# core.net
KiCad netlist of a schematic drawn in Altium Designer
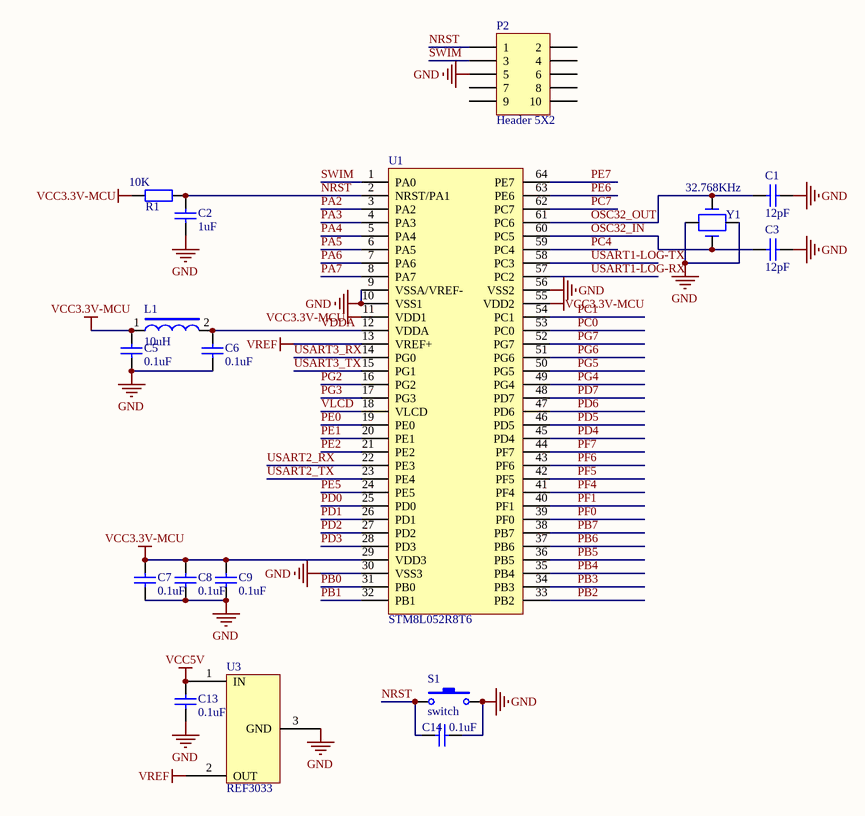
[diagram p0: core.SchDoc]

(export (version "E")
  (design (tool "Eeschema 10.0.6"))
  (components
    (comp (ref "C1")
      (value "12pF")
      (footprint "0603_C")
      (description "贴片电容，0603")
      (libsource (lib "stm8l052r8t6开发板") (part "Cap"))
    )
    (comp (ref "C2")
      (value "1uF")
      (footprint "0603_C")
      (description "贴片电容，0603")
      (libsource (lib "stm8l052r8t6开发板") (part "Cap"))
    )
    (comp (ref "C3")
      (value "12pF")
      (footprint "0603_C")
      (description "贴片电容，0603")
      (libsource (lib "stm8l052r8t6开发板") (part "Cap"))
    )
    (comp (ref "C5")
      (value "0.1uF")
      (footprint "0603_C")
      (description "贴片电容，0603")
      (libsource (lib "stm8l052r8t6开发板") (part "Cap"))
    )
    (comp (ref "C6")
      (value "0.1uF")
      (footprint "0603_C")
      (description "贴片电容，0603")
      (libsource (lib "stm8l052r8t6开发板") (part "Cap"))
    )
    (comp (ref "C7")
      (value "0.1uF")
      (footprint "0603_C")
      (description "贴片电容，0603")
      (libsource (lib "stm8l052r8t6开发板") (part "Cap"))
    )
    (comp (ref "C8")
      (value "0.1uF")
      (footprint "0603_C")
      (description "贴片电容，0603")
      (libsource (lib "stm8l052r8t6开发板") (part "Cap"))
    )
    (comp (ref "C9")
      (value "0.1uF")
      (footprint "0603_C")
      (description "贴片电容，0603")
      (libsource (lib "stm8l052r8t6开发板") (part "Cap"))
    )
    (comp (ref "C13")
      (value "0.1uF")
      (footprint "0603_C")
      (description "贴片电容，0603")
      (libsource (lib "stm8l052r8t6开发板") (part "Cap"))
    )
    (comp (ref "C14")
      (value "0.1uF")
      (footprint "0603_C")
      (description "贴片电容，0603")
      (libsource (lib "stm8l052r8t6开发板") (part "Cap"))
    )
    (comp (ref "L1")
      (value "10uH")
      (footprint "0603_L")
      (description "MLZ1608E100MT000，贴片电感，0603")
      (libsource (lib "stm8l052r8t6开发板") (part "L"))
    )
    (comp (ref "P2")
      (value "Header 5X2")
      (footprint "2.54-2*5P简牛")
      (description "2.54mm 2*5P 直 简牛")
      (libsource (lib "Miscellaneous Connectors") (part "Header 5X2"))
    )
    (comp (ref "R1")
      (value "10K")
      (footprint "0603_R")
      (description "贴片电阻，0603")
      (libsource (lib "stm8l052r8t6开发板") (part "Res2"))
    )
    (comp (ref "S1")
      (value "switch")
      (footprint "SW-SMD_4P-L6.2-W6.2-P4.50-LS9.0")
      (description "贴片按键，6*6*5")
      (libsource (lib "stm8l052r8t6开发板") (part "switch"))
    )
    (comp (ref "U1")
      (value "STM8L052R8T6")
      (footprint "LQFP-64_10X10X05P")
      (description "STM8L052R8T6,LQFP-64_10x10x05P")
      (libsource (lib "stm8l052r8t6开发板") (part "STM8L052R8T6"))
    )
    (comp (ref "U3")
      (value "REF3033")
      (footprint "SOT-23(SOT-23-3)")
      (description "3.0V标准电压输出，SOT-23")
      (fields (field (name "AUTOR") "caibin"))
      (libsource (lib "stm8l052r8t6开发板") (part "REF3033AIDBZR"))
    )
    (comp (ref "Y1")
      (value "32.768KHz")
      (footprint "CRY_MC146")
      (description "OSC,32.768KHz,+/-25ppm,3.3V,15pF,MC146,-20℃~70℃")
      (libsource (lib "stm8l052r8t6开发板") (part "CRYSTAL_1"))
    )
  )
  (nets
    (net (code "1") (name "/NRST") (class "Default")
      (node (ref "C14") (pin "1") (pinfunction "1_1") (pintype "passive"))
      (node (ref "C2") (pin "2") (pinfunction "2_2") (pintype "passive"))
      (node (ref "P2") (pin "1") (pinfunction "1_1") (pintype "passive"))
      (node (ref "R1") (pin "2") (pinfunction "2_2") (pintype "passive"))
      (node (ref "S1") (pin "1") (pinfunction "1_1") (pintype "passive"))
      (node (ref "U1") (pin "2") (pinfunction "NRST/PA1_2") (pintype "passive"))
    )
    (net (code "2") (name "/OSC32_IN") (class "Default")
      (node (ref "C3") (pin "2") (pinfunction "2_2") (pintype "passive"))
      (node (ref "U1") (pin "60") (pinfunction "PC5_60") (pintype "passive"))
      (node (ref "Y1") (pin "1") (pinfunction "1_1") (pintype "passive"))
    )
    (net (code "3") (name "/OSC32_OUT") (class "Default")
      (node (ref "C1") (pin "2") (pinfunction "2_2") (pintype "passive"))
      (node (ref "U1") (pin "61") (pinfunction "PC6_61") (pintype "passive"))
      (node (ref "Y1") (pin "2") (pinfunction "2_2") (pintype "passive"))
    )
    (net (code "4") (name "/PA2") (class "Default")
      (node (ref "U1") (pin "3") (pinfunction "PA2_3") (pintype "passive"))
    )
    (net (code "5") (name "/PA3") (class "Default")
      (node (ref "U1") (pin "4") (pinfunction "PA3_4") (pintype "passive"))
    )
    (net (code "6") (name "/PA4") (class "Default")
      (node (ref "U1") (pin "5") (pinfunction "PA4_5") (pintype "passive"))
    )
    (net (code "7") (name "/PA5") (class "Default")
      (node (ref "U1") (pin "6") (pinfunction "PA5_6") (pintype "passive"))
    )
    (net (code "8") (name "/PA6") (class "Default")
      (node (ref "U1") (pin "7") (pinfunction "PA6_7") (pintype "passive"))
    )
    (net (code "9") (name "/PA7") (class "Default")
      (node (ref "U1") (pin "8") (pinfunction "PA7_8") (pintype "passive"))
    )
    (net (code "10") (name "/PB0") (class "Default")
      (node (ref "U1") (pin "31") (pinfunction "PB0_31") (pintype "passive"))
    )
    (net (code "11") (name "/PB1") (class "Default")
      (node (ref "U1") (pin "32") (pinfunction "PB1_32") (pintype "passive"))
    )
    (net (code "12") (name "/PB2") (class "Default")
      (node (ref "U1") (pin "33") (pinfunction "PB2_33") (pintype "passive"))
    )
    (net (code "13") (name "/PB3") (class "Default")
      (node (ref "U1") (pin "34") (pinfunction "PB3_34") (pintype "passive"))
    )
    (net (code "14") (name "/PB4") (class "Default")
      (node (ref "U1") (pin "35") (pinfunction "PB4_35") (pintype "passive"))
    )
    (net (code "15") (name "/PB5") (class "Default")
      (node (ref "U1") (pin "36") (pinfunction "PB5_36") (pintype "passive"))
    )
    (net (code "16") (name "/PB6") (class "Default")
      (node (ref "U1") (pin "37") (pinfunction "PB6_37") (pintype "passive"))
    )
    (net (code "17") (name "/PB7") (class "Default")
      (node (ref "U1") (pin "38") (pinfunction "PB7_38") (pintype "passive"))
    )
    (net (code "18") (name "/PC0") (class "Default")
      (node (ref "U1") (pin "53") (pinfunction "PC0_53") (pintype "passive"))
    )
    (net (code "19") (name "/PC1") (class "Default")
      (node (ref "U1") (pin "54") (pinfunction "PC1_54") (pintype "passive"))
    )
    (net (code "20") (name "/PC4") (class "Default")
      (node (ref "U1") (pin "59") (pinfunction "PC4_59") (pintype "passive"))
    )
    (net (code "21") (name "/PC7") (class "Default")
      (node (ref "U1") (pin "62") (pinfunction "PC7_62") (pintype "passive"))
    )
    (net (code "22") (name "/PD0") (class "Default")
      (node (ref "U1") (pin "25") (pinfunction "PD0_25") (pintype "passive"))
    )
    (net (code "23") (name "/PD1") (class "Default")
      (node (ref "U1") (pin "26") (pinfunction "PD1_26") (pintype "passive"))
    )
    (net (code "24") (name "/PD2") (class "Default")
      (node (ref "U1") (pin "27") (pinfunction "PD2_27") (pintype "passive"))
    )
    (net (code "25") (name "/PD3") (class "Default")
      (node (ref "U1") (pin "28") (pinfunction "PD3_28") (pintype "passive"))
    )
    (net (code "26") (name "/PD4") (class "Default")
      (node (ref "U1") (pin "45") (pinfunction "PD4_45") (pintype "passive"))
    )
    (net (code "27") (name "/PD5") (class "Default")
      (node (ref "U1") (pin "46") (pinfunction "PD5_46") (pintype "passive"))
    )
    (net (code "28") (name "/PD6") (class "Default")
      (node (ref "U1") (pin "47") (pinfunction "PD6_47") (pintype "passive"))
    )
    (net (code "29") (name "/PD7") (class "Default")
      (node (ref "U1") (pin "48") (pinfunction "PD7_48") (pintype "passive"))
    )
    (net (code "30") (name "/PE0") (class "Default")
      (node (ref "U1") (pin "19") (pinfunction "PE0_19") (pintype "passive"))
    )
    (net (code "31") (name "/PE1") (class "Default")
      (node (ref "U1") (pin "20") (pinfunction "PE1_20") (pintype "passive"))
    )
    (net (code "32") (name "/PE2") (class "Default")
      (node (ref "U1") (pin "21") (pinfunction "PE2_21") (pintype "passive"))
    )
    (net (code "33") (name "/PE5") (class "Default")
      (node (ref "U1") (pin "24") (pinfunction "PE5_24") (pintype "passive"))
    )
    (net (code "34") (name "/PE6") (class "Default")
      (node (ref "U1") (pin "63") (pinfunction "PE6_63") (pintype "passive"))
    )
    (net (code "35") (name "/PE7") (class "Default")
      (node (ref "U1") (pin "64") (pinfunction "PE7_64") (pintype "passive"))
    )
    (net (code "36") (name "/PF0") (class "Default")
      (node (ref "U1") (pin "39") (pinfunction "PF0_39") (pintype "passive"))
    )
    (net (code "37") (name "/PF1") (class "Default")
      (node (ref "U1") (pin "40") (pinfunction "PF1_40") (pintype "passive"))
    )
    (net (code "38") (name "/PF4") (class "Default")
      (node (ref "U1") (pin "41") (pinfunction "PF4_41") (pintype "passive"))
    )
    (net (code "39") (name "/PF5") (class "Default")
      (node (ref "U1") (pin "42") (pinfunction "PF5_42") (pintype "passive"))
    )
    (net (code "40") (name "/PF6") (class "Default")
      (node (ref "U1") (pin "43") (pinfunction "PF6_43") (pintype "passive"))
    )
    (net (code "41") (name "/PF7") (class "Default")
      (node (ref "U1") (pin "44") (pinfunction "PF7_44") (pintype "passive"))
    )
    (net (code "42") (name "/PG2") (class "Default")
      (node (ref "U1") (pin "16") (pinfunction "PG2_16") (pintype "passive"))
    )
    (net (code "43") (name "/PG3") (class "Default")
      (node (ref "U1") (pin "17") (pinfunction "PG3_17") (pintype "passive"))
    )
    (net (code "44") (name "/PG4") (class "Default")
      (node (ref "U1") (pin "49") (pinfunction "PG4_49") (pintype "passive"))
    )
    (net (code "45") (name "/PG5") (class "Default")
      (node (ref "U1") (pin "50") (pinfunction "PG5_50") (pintype "passive"))
    )
    (net (code "46") (name "/PG6") (class "Default")
      (node (ref "U1") (pin "51") (pinfunction "PG6_51") (pintype "passive"))
    )
    (net (code "47") (name "/PG7") (class "Default")
      (node (ref "U1") (pin "52") (pinfunction "PG7_52") (pintype "passive"))
    )
    (net (code "48") (name "/SWIM") (class "Default")
      (node (ref "P2") (pin "3") (pinfunction "3_3") (pintype "passive"))
      (node (ref "U1") (pin "1") (pinfunction "PA0_1") (pintype "passive"))
    )
    (net (code "49") (name "/USART1-LOG-RX") (class "Default")
      (node (ref "U1") (pin "57") (pinfunction "PC2_57") (pintype "passive"))
    )
    (net (code "50") (name "/USART1-LOG-TX") (class "Default")
      (node (ref "U1") (pin "58") (pinfunction "PC3_58") (pintype "passive"))
    )
    (net (code "51") (name "/USART2_RX") (class "Default")
      (node (ref "U1") (pin "22") (pinfunction "PE3_22") (pintype "passive"))
    )
    (net (code "52") (name "/USART2_TX") (class "Default")
      (node (ref "U1") (pin "23") (pinfunction "PE4_23") (pintype "passive"))
    )
    (net (code "53") (name "/USART3_RX") (class "Default")
      (node (ref "U1") (pin "14") (pinfunction "PG0_14") (pintype "passive"))
    )
    (net (code "54") (name "/USART3_TX") (class "Default")
      (node (ref "U1") (pin "15") (pinfunction "PG1_15") (pintype "passive"))
    )
    (net (code "55") (name "/VDDA") (class "Default")
      (node (ref "C6") (pin "2") (pinfunction "2_2") (pintype "passive"))
      (node (ref "L1") (pin "2") (pintype "passive"))
      (node (ref "U1") (pin "12") (pinfunction "VDDA_12") (pintype "passive"))
    )
    (net (code "56") (name "/VLCD") (class "Default")
      (node (ref "U1") (pin "18") (pinfunction "VLCD_18") (pintype "passive"))
    )
    (net (code "57") (name "GND") (class "Default")
      (node (ref "C1") (pin "1") (pinfunction "1_1") (pintype "passive"))
      (node (ref "C13") (pin "1") (pinfunction "1_1") (pintype "passive"))
      (node (ref "C14") (pin "2") (pinfunction "2_2") (pintype "passive"))
      (node (ref "C2") (pin "1") (pinfunction "1_1") (pintype "passive"))
      (node (ref "C3") (pin "1") (pinfunction "1_1") (pintype "passive"))
      (node (ref "C5") (pin "1") (pinfunction "1_1") (pintype "passive"))
      (node (ref "C6") (pin "1") (pinfunction "1_1") (pintype "passive"))
      (node (ref "C7") (pin "1") (pinfunction "1_1") (pintype "passive"))
      (node (ref "C8") (pin "1") (pinfunction "1_1") (pintype "passive"))
      (node (ref "C9") (pin "1") (pinfunction "1_1") (pintype "passive"))
      (node (ref "P2") (pin "5") (pinfunction "5_5") (pintype "passive"))
      (node (ref "S1") (pin "2") (pinfunction "2_2") (pintype "passive"))
      (node (ref "U1") (pin "10") (pinfunction "VSS1_10") (pintype "passive"))
      (node (ref "U1") (pin "30") (pinfunction "VSS3_30") (pintype "passive"))
      (node (ref "U1") (pin "56") (pinfunction "VSS2_56") (pintype "passive"))
      (node (ref "U1") (pin "9") (pinfunction "VSSA/VREF-_9") (pintype "passive"))
      (node (ref "U3") (pin "3") (pinfunction "GND_3") (pintype "passive"))
      (node (ref "Y1") (pin "3") (pinfunction "3_3") (pintype "passive"))
      (node (ref "Y1") (pin "4") (pinfunction "4_4") (pintype "passive"))
    )
    (net (code "58") (name "VCC3.3V-MCU") (class "Default")
      (node (ref "C5") (pin "2") (pinfunction "2_2") (pintype "passive"))
      (node (ref "C7") (pin "2") (pinfunction "2_2") (pintype "passive"))
      (node (ref "C8") (pin "2") (pinfunction "2_2") (pintype "passive"))
      (node (ref "C9") (pin "2") (pinfunction "2_2") (pintype "passive"))
      (node (ref "L1") (pin "1") (pintype "passive"))
      (node (ref "R1") (pin "1") (pinfunction "1_1") (pintype "passive"))
      (node (ref "U1") (pin "11") (pinfunction "VDD1_11") (pintype "passive"))
      (node (ref "U1") (pin "29") (pinfunction "VDD3_29") (pintype "passive"))
      (node (ref "U1") (pin "55") (pinfunction "VDD2_55") (pintype "passive"))
    )
    (net (code "59") (name "VCC5V") (class "Default")
      (node (ref "C13") (pin "2") (pinfunction "2_2") (pintype "passive"))
      (node (ref "U3") (pin "1") (pinfunction "IN_1") (pintype "passive"))
    )
    (net (code "60") (name "VREF") (class "Default")
      (node (ref "U1") (pin "13") (pinfunction "VREF+_13") (pintype "passive"))
      (node (ref "U3") (pin "2") (pinfunction "OUT_2") (pintype "passive"))
    )
    (net (code "61") (name "unconnected-(P2-Pad2)") (class "Default")
      (node (ref "P2") (pin "2") (pinfunction "2_2") (pintype "passive"))
    )
    (net (code "62") (name "unconnected-(P2-Pad4)") (class "Default")
      (node (ref "P2") (pin "4") (pinfunction "4_4") (pintype "passive"))
    )
    (net (code "63") (name "unconnected-(P2-Pad6)") (class "Default")
      (node (ref "P2") (pin "6") (pinfunction "6_6") (pintype "passive"))
    )
    (net (code "64") (name "unconnected-(P2-Pad7)") (class "Default")
      (node (ref "P2") (pin "7") (pinfunction "7_7") (pintype "passive"))
    )
    (net (code "65") (name "unconnected-(P2-Pad8)") (class "Default")
      (node (ref "P2") (pin "8") (pinfunction "8_8") (pintype "passive"))
    )
    (net (code "66") (name "unconnected-(P2-Pad9)") (class "Default")
      (node (ref "P2") (pin "9") (pinfunction "9_9") (pintype "passive"))
    )
    (net (code "67") (name "unconnected-(P2-Pad10)") (class "Default")
      (node (ref "P2") (pin "10") (pinfunction "10_10") (pintype "passive"))
    )
  )
)
